# MusselTracker2_RevC.net
KiCad netlist of a schematic drawn in EAGLE
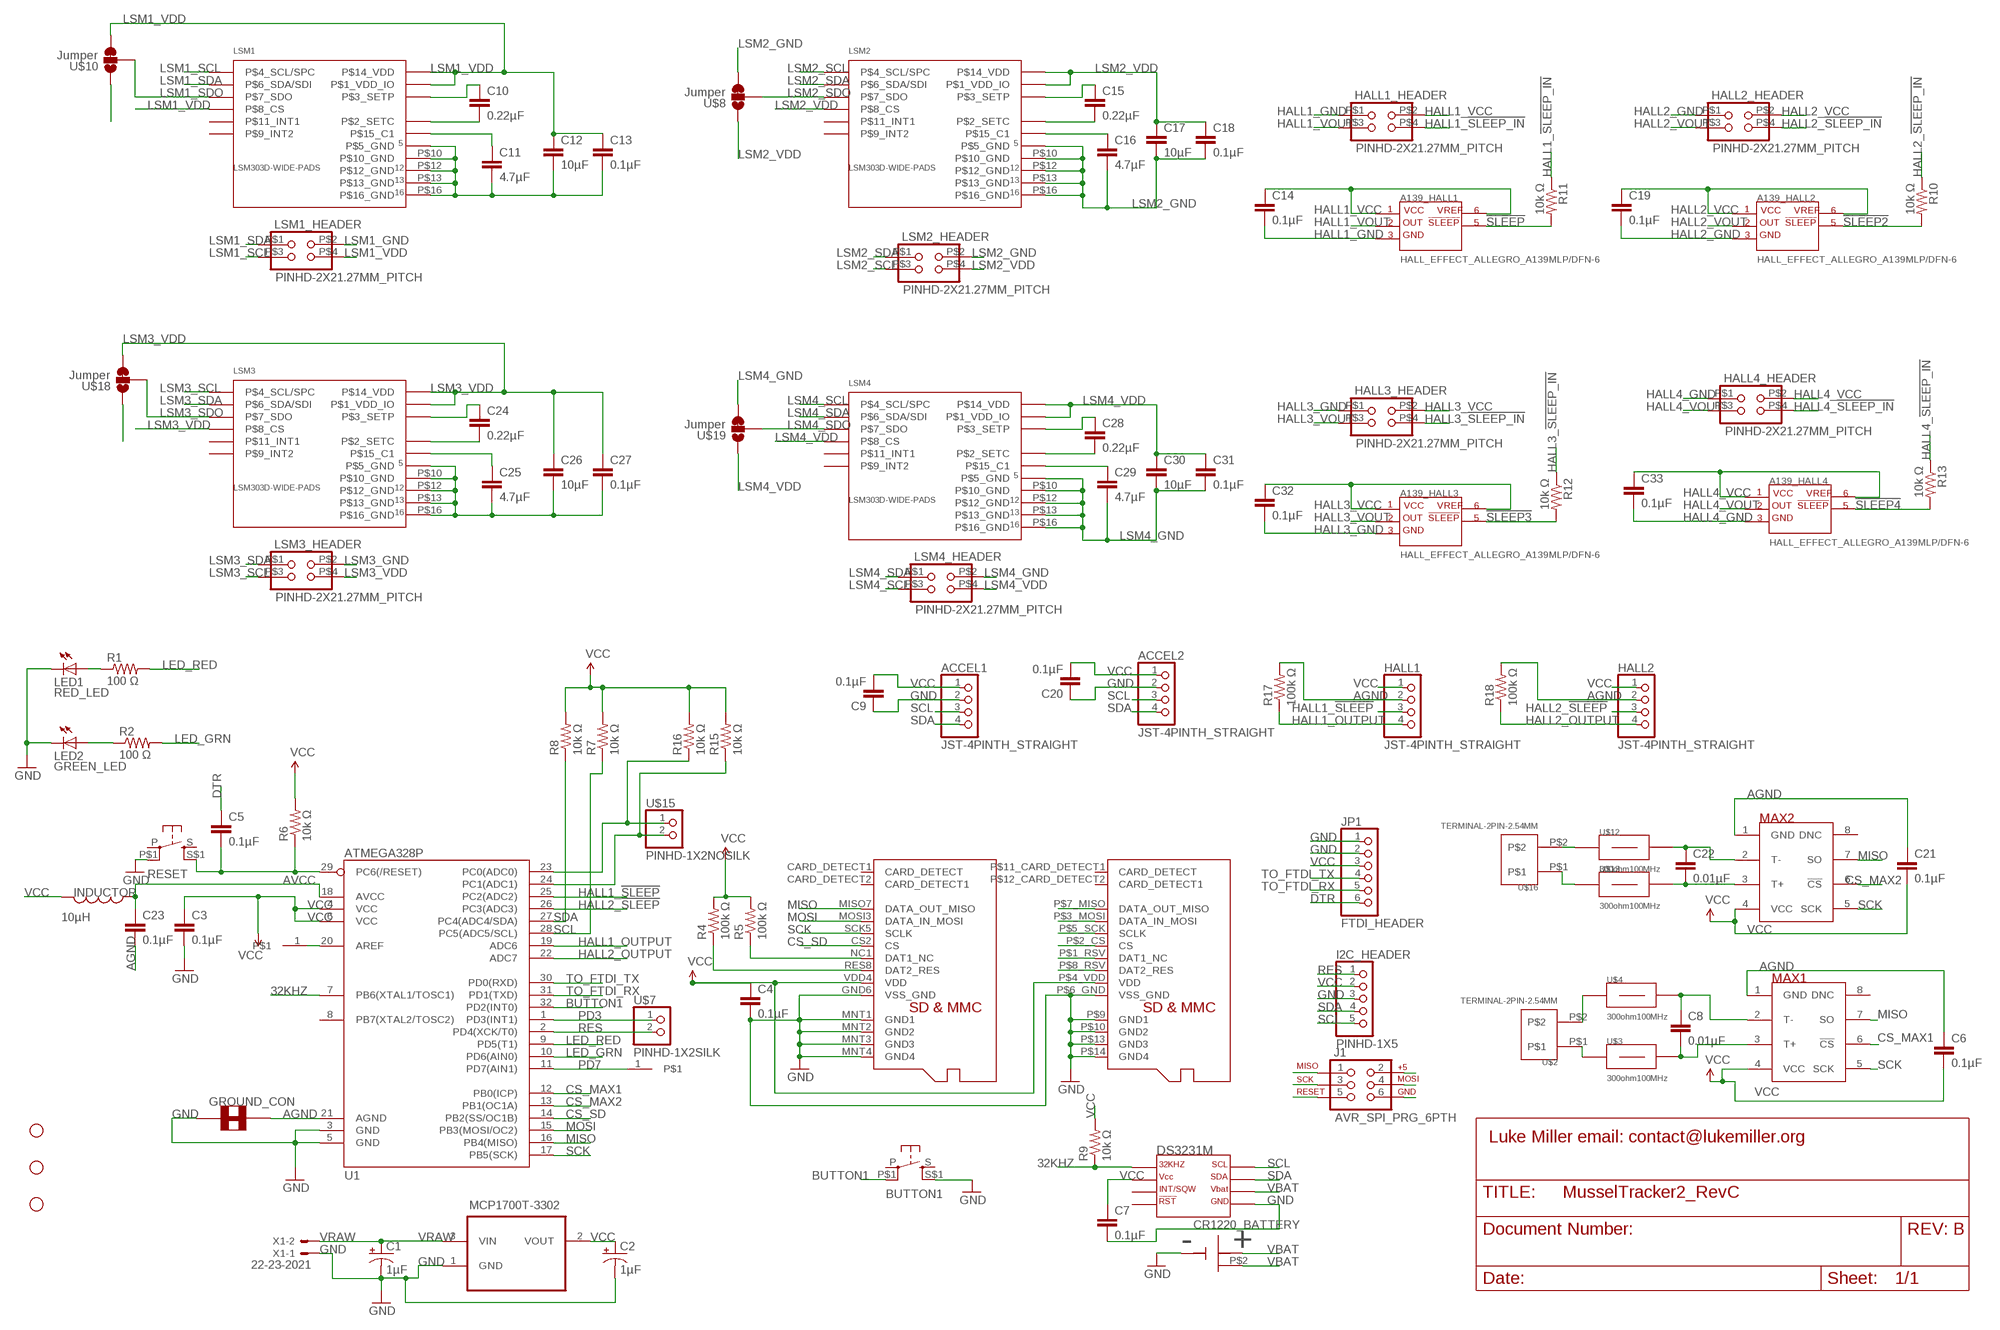
[diagram p0: schematic, sheet 1]

(export (version "E")
  (design (tool "Eeschema 10.0.6"))
  (components
    (comp (ref "A139_HALL1")
      (value "HALL_EFFECT_ALLEGRO_A139MLP/DFN-6")
      (footprint "eagle-import:A139__HALL_EFFECT")
      (libsource (lib "eagle-import") (part "HALL_EFFECT_ALLEGRO_A139MLP/DFN-6"))
    )
    (comp (ref "A139_HALL2")
      (value "HALL_EFFECT_ALLEGRO_A139MLP/DFN-6")
      (footprint "eagle-import:A139__HALL_EFFECT")
      (libsource (lib "eagle-import") (part "HALL_EFFECT_ALLEGRO_A139MLP/DFN-6"))
    )
    (comp (ref "A139_HALL3")
      (value "HALL_EFFECT_ALLEGRO_A139MLP/DFN-6")
      (footprint "eagle-import:A139__HALL_EFFECT")
      (libsource (lib "eagle-import") (part "HALL_EFFECT_ALLEGRO_A139MLP/DFN-6"))
    )
    (comp (ref "A139_HALL4")
      (value "HALL_EFFECT_ALLEGRO_A139MLP/DFN-6")
      (footprint "eagle-import:A139__HALL_EFFECT")
      (libsource (lib "eagle-import") (part "HALL_EFFECT_ALLEGRO_A139MLP/DFN-6"))
    )
    (comp (ref "ACCEL1")
      (value "JST-4PINTH_STRAIGHT")
      (footprint "eagle-import:JST-PH-4-THM")
      (libsource (lib "eagle-import") (part "JST-4PINTH_STRAIGHT"))
    )
    (comp (ref "ACCEL2")
      (value "JST-4PINTH_STRAIGHT")
      (footprint "eagle-import:JST-PH-4-THM")
      (libsource (lib "eagle-import") (part "JST-4PINTH_STRAIGHT"))
    )
    (comp (ref "BUTTON1")
      (value "PUSHBUTTON_DPST_SMD")
      (footprint "eagle-import:PUSHBUTTON_DPST_SMD")
      (libsource (lib "eagle-import") (part "PUSHBUTTON_DPST_SMD"))
    )
    (comp (ref "C1")
      (value "1µF")
      (footprint "eagle-import:PANASONIC_B")
      (libsource (lib "eagle-import") (part "CPOL-USB"))
    )
    (comp (ref "C2")
      (value "1µF")
      (footprint "eagle-import:PANASONIC_B")
      (libsource (lib "eagle-import") (part "CPOL-USB"))
    )
    (comp (ref "C3")
      (value "0.1µF")
      (footprint "eagle-import:0805")
      (libsource (lib "eagle-import") (part "CAP0805"))
    )
    (comp (ref "C4")
      (value "0.1µF")
      (footprint "eagle-import:0805")
      (libsource (lib "eagle-import") (part "CAP0805"))
    )
    (comp (ref "C5")
      (value "0.1µF")
      (footprint "eagle-import:0805")
      (libsource (lib "eagle-import") (part "CAP0805"))
    )
    (comp (ref "C6")
      (value "0.1µF")
      (footprint "eagle-import:0805")
      (libsource (lib "eagle-import") (part "CAP0805"))
    )
    (comp (ref "C7")
      (value "0.1µF")
      (footprint "eagle-import:0805")
      (libsource (lib "eagle-import") (part "CAP0805"))
    )
    (comp (ref "C8")
      (value "0.01µF")
      (footprint "eagle-import:0805_CAP_50V_KEMET")
      (libsource (lib "eagle-import") (part "CAP0805_KEMET"))
    )
    (comp (ref "C9")
      (value "0.1µF")
      (footprint "eagle-import:0805")
      (libsource (lib "eagle-import") (part "CAP0805"))
    )
    (comp (ref "C10")
      (value "0.22µF")
      (footprint "eagle-import:0805")
      (libsource (lib "eagle-import") (part "CAP0805"))
    )
    (comp (ref "C11")
      (value "4.7µF")
      (footprint "eagle-import:0805")
      (libsource (lib "eagle-import") (part "CAP0805"))
    )
    (comp (ref "C12")
      (value "10µF")
      (footprint "eagle-import:0805")
      (libsource (lib "eagle-import") (part "CAP0805"))
    )
    (comp (ref "C13")
      (value "0.1µF")
      (footprint "eagle-import:0805")
      (libsource (lib "eagle-import") (part "CAP0805"))
    )
    (comp (ref "C14")
      (value "0.1µF")
      (footprint "eagle-import:0805")
      (libsource (lib "eagle-import") (part "CAP0805"))
    )
    (comp (ref "C15")
      (value "0.22µF")
      (footprint "eagle-import:0805")
      (libsource (lib "eagle-import") (part "CAP0805"))
    )
    (comp (ref "C16")
      (value "4.7µF")
      (footprint "eagle-import:0805")
      (libsource (lib "eagle-import") (part "CAP0805"))
    )
    (comp (ref "C17")
      (value "10µF")
      (footprint "eagle-import:0805")
      (libsource (lib "eagle-import") (part "CAP0805"))
    )
    (comp (ref "C18")
      (value "0.1µF")
      (footprint "eagle-import:0805")
      (libsource (lib "eagle-import") (part "CAP0805"))
    )
    (comp (ref "C19")
      (value "0.1µF")
      (footprint "eagle-import:0805")
      (libsource (lib "eagle-import") (part "CAP0805"))
    )
    (comp (ref "C20")
      (value "0.1µF")
      (footprint "eagle-import:0805")
      (libsource (lib "eagle-import") (part "CAP0805"))
    )
    (comp (ref "C21")
      (value "0.1µF")
      (footprint "eagle-import:0805")
      (libsource (lib "eagle-import") (part "CAP0805"))
    )
    (comp (ref "C22")
      (value "0.01µF")
      (footprint "eagle-import:0805_CAP_50V_KEMET")
      (libsource (lib "eagle-import") (part "CAP0805_KEMET"))
    )
    (comp (ref "C23")
      (value "0.1µF")
      (footprint "eagle-import:0805")
      (libsource (lib "eagle-import") (part "CAP0805"))
    )
    (comp (ref "C24")
      (value "0.22µF")
      (footprint "eagle-import:0805")
      (libsource (lib "eagle-import") (part "CAP0805"))
    )
    (comp (ref "C25")
      (value "4.7µF")
      (footprint "eagle-import:0805")
      (libsource (lib "eagle-import") (part "CAP0805"))
    )
    (comp (ref "C26")
      (value "10µF")
      (footprint "eagle-import:0805")
      (libsource (lib "eagle-import") (part "CAP0805"))
    )
    (comp (ref "C27")
      (value "0.1µF")
      (footprint "eagle-import:0805")
      (libsource (lib "eagle-import") (part "CAP0805"))
    )
    (comp (ref "C28")
      (value "0.22µF")
      (footprint "eagle-import:0805")
      (libsource (lib "eagle-import") (part "CAP0805"))
    )
    (comp (ref "C29")
      (value "4.7µF")
      (footprint "eagle-import:0805")
      (libsource (lib "eagle-import") (part "CAP0805"))
    )
    (comp (ref "C30")
      (value "10µF")
      (footprint "eagle-import:0805")
      (libsource (lib "eagle-import") (part "CAP0805"))
    )
    (comp (ref "C31")
      (value "0.1µF")
      (footprint "eagle-import:0805")
      (libsource (lib "eagle-import") (part "CAP0805"))
    )
    (comp (ref "C32")
      (value "0.1µF")
      (footprint "eagle-import:0805")
      (libsource (lib "eagle-import") (part "CAP0805"))
    )
    (comp (ref "C33")
      (value "0.1µF")
      (footprint "eagle-import:0805")
      (libsource (lib "eagle-import") (part "CAP0805"))
    )
    (comp (ref "CR1220_BATTERY")
      (value "CR1220_BATTERY_HOLDERSMD")
      (footprint "eagle-import:CR1220_BATTERY_HOLDER_SMD")
      (libsource (lib "eagle-import") (part "CR1220_BATTERY_HOLDERSMD"))
    )
    (comp (ref "DS3231M")
      (value "DS3231MSOIC-8")
      (footprint "eagle-import:DS3231M_SOIC8")
      (libsource (lib "eagle-import") (part "DS3231MSOIC-8"))
    )
    (comp (ref "GROUND_CON")
      (value "SOLDER_JUMPER_TRACESTANDARD")
      (footprint "eagle-import:SJ_2S-TRACE")
      (libsource (lib "eagle-import") (part "SOLDER_JUMPER_TRACESTANDARD"))
    )
    (comp (ref "HALL1")
      (value "JST-4PINTH_STRAIGHT")
      (footprint "eagle-import:JST-PH-4-THM")
      (libsource (lib "eagle-import") (part "JST-4PINTH_STRAIGHT"))
    )
    (comp (ref "HALL1_HEADER")
      (value "PINHD-2X21.27MM_PITCH")
      (footprint "eagle-import:2X2_1.27MM")
      (libsource (lib "eagle-import") (part "PINHD-2X21.27MM_PITCH"))
    )
    (comp (ref "HALL2")
      (value "JST-4PINTH_STRAIGHT")
      (footprint "eagle-import:JST-PH-4-THM")
      (libsource (lib "eagle-import") (part "JST-4PINTH_STRAIGHT"))
    )
    (comp (ref "HALL2_HEADER")
      (value "PINHD-2X21.27MM_PITCH")
      (footprint "eagle-import:2X2_1.27MM")
      (libsource (lib "eagle-import") (part "PINHD-2X21.27MM_PITCH"))
    )
    (comp (ref "HALL3_HEADER")
      (value "PINHD-2X21.27MM_PITCH")
      (footprint "eagle-import:2X2_1.27MM")
      (libsource (lib "eagle-import") (part "PINHD-2X21.27MM_PITCH"))
    )
    (comp (ref "HALL4_HEADER")
      (value "PINHD-2X21.27MM_PITCH")
      (footprint "eagle-import:2X2_1.27MM")
      (libsource (lib "eagle-import") (part "PINHD-2X21.27MM_PITCH"))
    )
    (comp (ref "I2C_HEADER")
      (value "PINHD-1X5")
      (footprint "eagle-import:1X05_BIGLOCK")
      (libsource (lib "eagle-import") (part "PINHD-1X5"))
    )
    (comp (ref "INDUCTOR")
      (value "10µH")
      (footprint "eagle-import:I_0805")
      (libsource (lib "eagle-import") (part "INDUCTOR0805_TY"))
    )
    (comp (ref "J1")
      (value "AVR_SPI_PRG_6PTH")
      (footprint "eagle-import:2X3")
      (libsource (lib "eagle-import") (part "AVR_SPI_PRG_6PTH"))
    )
    (comp (ref "JP1")
      (value "FTDI_HEADER")
      (footprint "eagle-import:1X06-BIGLOCK")
      (libsource (lib "eagle-import") (part "PINHD-1X6LOCK"))
    )
    (comp (ref "LED1")
      (value "RED_LED")
      (footprint "eagle-import:CHIPLED_0805")
      (libsource (lib "eagle-import") (part "LED0805"))
    )
    (comp (ref "LED2")
      (value "GREEN_LED")
      (footprint "eagle-import:CHIPLED_0805")
      (libsource (lib "eagle-import") (part "LED0805"))
    )
    (comp (ref "LSM1")
      (value "LSM303D-WIDE-PADS")
      (footprint "eagle-import:LSM303D")
      (libsource (lib "eagle-import") (part "LSM303D-WIDE-PADS"))
    )
    (comp (ref "LSM1_HEADER")
      (value "PINHD-2X21.27MM_PITCH")
      (footprint "eagle-import:2X2_1.27MM")
      (libsource (lib "eagle-import") (part "PINHD-2X21.27MM_PITCH"))
    )
    (comp (ref "LSM2")
      (value "LSM303D-WIDE-PADS")
      (footprint "eagle-import:LSM303D")
      (libsource (lib "eagle-import") (part "LSM303D-WIDE-PADS"))
    )
    (comp (ref "LSM2_HEADER")
      (value "PINHD-2X21.27MM_PITCH")
      (footprint "eagle-import:2X2_1.27MM")
      (libsource (lib "eagle-import") (part "PINHD-2X21.27MM_PITCH"))
    )
    (comp (ref "LSM3")
      (value "LSM303D-WIDE-PADS")
      (footprint "eagle-import:LSM303D")
      (libsource (lib "eagle-import") (part "LSM303D-WIDE-PADS"))
    )
    (comp (ref "LSM3_HEADER")
      (value "PINHD-2X21.27MM_PITCH")
      (footprint "eagle-import:2X2_1.27MM")
      (libsource (lib "eagle-import") (part "PINHD-2X21.27MM_PITCH"))
    )
    (comp (ref "LSM4")
      (value "LSM303D-WIDE-PADS")
      (footprint "eagle-import:LSM303D")
      (libsource (lib "eagle-import") (part "LSM303D-WIDE-PADS"))
    )
    (comp (ref "LSM4_HEADER")
      (value "PINHD-2X21.27MM_PITCH")
      (footprint "eagle-import:2X2_1.27MM")
      (libsource (lib "eagle-import") (part "PINHD-2X21.27MM_PITCH"))
    )
    (comp (ref "MAX1")
      (value "MAX31855")
      (footprint "eagle-import:SO08")
      (libsource (lib "eagle-import") (part "MAX31855"))
    )
    (comp (ref "MAX2")
      (value "MAX31855")
      (footprint "eagle-import:SO08")
      (libsource (lib "eagle-import") (part "MAX31855"))
    )
    (comp (ref "MCP1700T-3302")
      (value "MCP1700T-3302E/TT")
      (footprint "eagle-import:SOT95P237X112-3N")
      (libsource (lib "eagle-import") (part "MCP1700T-3302E/TT"))
    )
    (comp (ref "R1")
      (value "100 Ω")
      (footprint "eagle-import:R0805")
      (libsource (lib "eagle-import") (part "RESISTOR_SMDR0805"))
    )
    (comp (ref "R2")
      (value "100 Ω")
      (footprint "eagle-import:R0805")
      (libsource (lib "eagle-import") (part "RESISTOR_SMDR0805"))
    )
    (comp (ref "R4")
      (value "100k Ω")
      (footprint "eagle-import:R0805")
      (libsource (lib "eagle-import") (part "RESISTOR_SMDR0805"))
    )
    (comp (ref "R5")
      (value "100k Ω")
      (footprint "eagle-import:R0805")
      (libsource (lib "eagle-import") (part "RESISTOR_SMDR0805"))
    )
    (comp (ref "R6")
      (value "10k Ω")
      (footprint "eagle-import:R0805")
      (libsource (lib "eagle-import") (part "RESISTOR_SMDR0805"))
    )
    (comp (ref "R7")
      (value "10k Ω")
      (footprint "eagle-import:R0805")
      (libsource (lib "eagle-import") (part "RESISTOR_SMDR0805"))
    )
    (comp (ref "R8")
      (value "10k Ω")
      (footprint "eagle-import:R0805")
      (libsource (lib "eagle-import") (part "RESISTOR_SMDR0805"))
    )
    (comp (ref "R9")
      (value "10k Ω")
      (footprint "eagle-import:R0805")
      (libsource (lib "eagle-import") (part "RESISTOR_SMDR0805"))
    )
    (comp (ref "R10")
      (value "10k Ω")
      (footprint "eagle-import:R0805")
      (libsource (lib "eagle-import") (part "RESISTOR_SMDR0805"))
    )
    (comp (ref "R11")
      (value "10k Ω")
      (footprint "eagle-import:R0805")
      (libsource (lib "eagle-import") (part "RESISTOR_SMDR0805"))
    )
    (comp (ref "R12")
      (value "10k Ω")
      (footprint "eagle-import:R0805")
      (libsource (lib "eagle-import") (part "RESISTOR_SMDR0805"))
    )
    (comp (ref "R13")
      (value "10k Ω")
      (footprint "eagle-import:R0805")
      (libsource (lib "eagle-import") (part "RESISTOR_SMDR0805"))
    )
    (comp (ref "R15")
      (value "10k Ω")
      (footprint "eagle-import:R0805")
      (libsource (lib "eagle-import") (part "RESISTOR_SMDR0805"))
    )
    (comp (ref "R16")
      (value "10k Ω")
      (footprint "eagle-import:R0805")
      (libsource (lib "eagle-import") (part "RESISTOR_SMDR0805"))
    )
    (comp (ref "R17")
      (value "100k Ω")
      (footprint "eagle-import:R0805")
      (libsource (lib "eagle-import") (part "RESISTOR_SMDR0805"))
    )
    (comp (ref "R18")
      (value "100k Ω")
      (footprint "eagle-import:R0805")
      (libsource (lib "eagle-import") (part "RESISTOR_SMDR0805"))
    )
    (comp (ref "RESET")
      (value "PUSHBUTTON_DPST_SMD")
      (footprint "eagle-import:PUSHBUTTON_DPST_SMD")
      (libsource (lib "eagle-import") (part "PUSHBUTTON_DPST_SMD"))
    )
    (comp (ref "STANDOFF1")
      (value "STAND-OFF")
      (footprint "eagle-import:STAND-OFF")
      (libsource (lib "eagle-import") (part "STAND-OFF"))
    )
    (comp (ref "STANDOFF2")
      (value "STAND-OFF")
      (footprint "eagle-import:STAND-OFF")
      (libsource (lib "eagle-import") (part "STAND-OFF"))
    )
    (comp (ref "STANDOFF3")
      (value "STAND-OFF")
      (footprint "eagle-import:STAND-OFF")
      (libsource (lib "eagle-import") (part "STAND-OFF"))
    )
    (comp (ref "U$1")
      (value "MICROSD_MOLEX_REVERSECURRENT")
      (footprint "eagle-import:MICROSD_SOCKET_MOLEX_REVERSEMOUNT")
      (libsource (lib "eagle-import") (part "MICROSD_MOLEX_REVERSECURRENT"))
    )
    (comp (ref "U$2")
      (value "TERMINAL-2PIN-2.54MM")
      (footprint "eagle-import:TERMINAL-2PIN-2.54MM")
      (libsource (lib "eagle-import") (part "TERMINAL-2PIN-2.54MM"))
    )
    (comp (ref "U$3")
      (value "300ohm100MHz")
      (footprint "eagle-import:0805")
      (libsource (lib "eagle-import") (part "FERRITE_BEAD0805"))
    )
    (comp (ref "U$4")
      (value "300ohm100MHz")
      (footprint "eagle-import:0805")
      (libsource (lib "eagle-import") (part "FERRITE_BEAD0805"))
    )
    (comp (ref "U$6")
      (value "PINHD-1X1SMALL")
      (footprint "eagle-import:1X01_SMALL")
      (libsource (lib "eagle-import") (part "PINHD-1X1SMALL"))
    )
    (comp (ref "U$7")
      (value "PINHD-1X2SILK")
      (footprint "eagle-import:1X02")
      (libsource (lib "eagle-import") (part "PINHD-1X2SILK"))
    )
    (comp (ref "U$8")
      (value "Jumper")
      (footprint "eagle-import:PAD-JUMPER-3-2OF3_NC_BY_TRACE_SMALL")
      (libsource (lib "eagle-import") (part "SOLDER_JUMPER_3_2OF3_NORMALLY_CLOSED_BY_TRACESMALL"))
    )
    (comp (ref "U$10")
      (value "Jumper")
      (footprint "eagle-import:PAD-JUMPER-3-2OF3_NC_BY_TRACE_SMALL")
      (libsource (lib "eagle-import") (part "SOLDER_JUMPER_3_2OF3_NORMALLY_CLOSED_BY_TRACESMALL"))
    )
    (comp (ref "U$12")
      (value "300ohm100MHz")
      (footprint "eagle-import:0805")
      (libsource (lib "eagle-import") (part "FERRITE_BEAD0805"))
    )
    (comp (ref "U$13")
      (value "300ohm100MHz")
      (footprint "eagle-import:0805")
      (libsource (lib "eagle-import") (part "FERRITE_BEAD0805"))
    )
    (comp (ref "U$14")
      (value "MICROSD_MOLEX_REVERSEOBSOLETE")
      (footprint "eagle-import:MICROSD_SOCKET_MOLEX_REVERSEMOUNT_OBSOLETE")
      (libsource (lib "eagle-import") (part "MICROSD_MOLEX_REVERSEOBSOLETE"))
    )
    (comp (ref "U$15")
      (value "PINHD-1X2NOSILK")
      (footprint "eagle-import:1X02_NOSILK")
      (libsource (lib "eagle-import") (part "PINHD-1X2NOSILK"))
    )
    (comp (ref "U$16")
      (value "TERMINAL-2PIN-2.54MM")
      (footprint "eagle-import:TERMINAL-2PIN-2.54MM")
      (libsource (lib "eagle-import") (part "TERMINAL-2PIN-2.54MM"))
    )
    (comp (ref "U$17")
      (value "PINHD-1X1SMALL")
      (footprint "eagle-import:1X01_SMALL")
      (libsource (lib "eagle-import") (part "PINHD-1X1SMALL"))
    )
    (comp (ref "U$18")
      (value "Jumper")
      (footprint "eagle-import:PAD-JUMPER-3-2OF3_NC_BY_TRACE_SMALL")
      (libsource (lib "eagle-import") (part "SOLDER_JUMPER_3_2OF3_NORMALLY_CLOSED_BY_TRACESMALL"))
    )
    (comp (ref "U$19")
      (value "Jumper")
      (footprint "eagle-import:PAD-JUMPER-3-2OF3_NC_BY_TRACE_SMALL")
      (libsource (lib "eagle-import") (part "SOLDER_JUMPER_3_2OF3_NORMALLY_CLOSED_BY_TRACESMALL"))
    )
    (comp (ref "U1")
      (value "ATMEGA328P")
      (footprint "eagle-import:TQFP32-08")
      (libsource (lib "eagle-import") (part "ATMEGA328_SMT"))
    )
    (comp (ref "X1")
      (value "22-23-2021")
      (footprint "eagle-import:22-23-2021")
      (fields (field (name "MF") "MOLEX"))
      (libsource (lib "eagle-import") (part "22-23-2021"))
    )
  )
  (nets
    (net (code "1") (name "/32KHZ") (class "Default")
      (node (ref "DS3231M") (pin "1") (pinfunction "P$1_32KHZ_1") (pintype "bidirectional"))
      (node (ref "R9") (pin "1") (pinfunction "1_1") (pintype "passive"))
      (node (ref "U1") (pin "7") (pinfunction "PB6(XTAL1/TOSC1)_7") (pintype "bidirectional"))
    )
    (net (code "2") (name "/AGND") (class "Default")
      (node (ref "C21") (pin "1") (pinfunction "1_1") (pintype "passive"))
      (node (ref "C23") (pin "2") (pinfunction "2_2") (pintype "passive"))
      (node (ref "C6") (pin "1") (pinfunction "1_1") (pintype "passive"))
      (node (ref "GROUND_CON") (pin "2") (pinfunction "P$2_2") (pintype "bidirectional"))
      (node (ref "HALL1") (pin "2") (pinfunction "2_2") (pintype "passive"))
      (node (ref "HALL2") (pin "2") (pinfunction "2_2") (pintype "passive"))
      (node (ref "MAX1") (pin "1") (pinfunction "GND_1") (pintype "power_in"))
      (node (ref "MAX2") (pin "1") (pinfunction "GND_1") (pintype "power_in"))
      (node (ref "R17") (pin "2") (pinfunction "2_2") (pintype "passive"))
      (node (ref "R18") (pin "2") (pinfunction "2_2") (pintype "passive"))
      (node (ref "U1") (pin "21") (pinfunction "AGND_21") (pintype "bidirectional"))
    )
    (net (code "3") (name "/AVCC") (class "Default")
      (node (ref "C23") (pin "1") (pinfunction "1_1") (pintype "passive"))
      (node (ref "INDUCTOR") (pin "P$1") (pinfunction "1_P$1") (pintype "passive"))
      (node (ref "U1") (pin "18") (pinfunction "AVCC_18") (pintype "bidirectional"))
    )
    (net (code "4") (name "/BUTTON1") (class "Default")
      (node (ref "BUTTON1") (pin "P$1") (pinfunction "P1_P$1") (pintype "passive"))
      (node (ref "U1") (pin "32") (pinfunction "PD2(INT0)_32") (pintype "bidirectional"))
    )
    (net (code "5") (name "/CS_MAX1") (class "Default")
      (node (ref "MAX1") (pin "6") (pinfunction "~{CS}_6") (pintype "bidirectional"))
      (node (ref "U1") (pin "12") (pinfunction "PB0(ICP)_12") (pintype "bidirectional"))
    )
    (net (code "6") (name "/CS_MAX2") (class "Default")
      (node (ref "MAX2") (pin "6") (pinfunction "~{CS}_6") (pintype "bidirectional"))
      (node (ref "U1") (pin "13") (pinfunction "PB1(OC1A)_13") (pintype "bidirectional"))
    )
    (net (code "7") (name "/CS_SD") (class "Default")
      (node (ref "U$1") (pin "CS2") (pinfunction "CS_CS2") (pintype "input"))
      (node (ref "U$14") (pin "P$2_CS") (pinfunction "CS_P$2_CS") (pintype "input"))
      (node (ref "U1") (pin "14") (pinfunction "PB2(SS/OC1B)_14") (pintype "bidirectional"))
    )
    (net (code "8") (name "/DTR") (class "Default")
      (node (ref "C5") (pin "1") (pinfunction "1_1") (pintype "passive"))
      (node (ref "JP1") (pin "6") (pinfunction "6_6") (pintype "passive"))
    )
    (net (code "9") (name "/HALL1_GND") (class "Default")
      (node (ref "A139_HALL1") (pin "P$3_4") (pinfunction "P$3_P$3_4") (pintype "bidirectional"))
      (node (ref "C14") (pin "2") (pinfunction "2_2") (pintype "passive"))
      (node (ref "HALL1_HEADER") (pin "P$1") (pinfunction "1_P$1") (pintype "passive"))
    )
    (net (code "10") (name "/HALL1_OUTPUT") (class "Default")
      (node (ref "HALL1") (pin "4") (pinfunction "4_4") (pintype "passive"))
      (node (ref "R17") (pin "1") (pinfunction "1_1") (pintype "passive"))
      (node (ref "U1") (pin "19") (pinfunction "ADC6_19") (pintype "bidirectional"))
    )
    (net (code "11") (name "/HALL1_VCC") (class "Default")
      (node (ref "A139_HALL1") (pin "P$1") (pinfunction "P$1_P$1") (pintype "bidirectional"))
      (node (ref "A139_HALL1") (pin "P$6") (pinfunction "P$6_P$6") (pintype "bidirectional"))
      (node (ref "C14") (pin "1") (pinfunction "1_1") (pintype "passive"))
      (node (ref "HALL1_HEADER") (pin "P$2") (pinfunction "2_P$2") (pintype "passive"))
    )
    (net (code "12") (name "/HALL1_VOUT") (class "Default")
      (node (ref "A139_HALL1") (pin "P$2") (pinfunction "P$2_P$2") (pintype "bidirectional"))
      (node (ref "HALL1_HEADER") (pin "P$3") (pinfunction "3_P$3") (pintype "passive"))
    )
    (net (code "13") (name "/HALL1_~{SLEEP_IN}") (class "Default")
      (node (ref "HALL1_HEADER") (pin "P$4") (pinfunction "4_P$4") (pintype "passive"))
      (node (ref "R11") (pin "1") (pinfunction "1_1") (pintype "passive"))
    )
    (net (code "14") (name "/HALL1_~{SLEEP}") (class "Default")
      (node (ref "HALL1") (pin "3") (pinfunction "3_3") (pintype "passive"))
      (node (ref "U1") (pin "25") (pinfunction "PC2(ADC2)_25") (pintype "bidirectional"))
    )
    (net (code "15") (name "/HALL2_GND") (class "Default")
      (node (ref "A139_HALL2") (pin "P$3_4") (pinfunction "P$3_P$3_4") (pintype "bidirectional"))
      (node (ref "C19") (pin "2") (pinfunction "2_2") (pintype "passive"))
      (node (ref "HALL2_HEADER") (pin "P$1") (pinfunction "1_P$1") (pintype "passive"))
    )
    (net (code "16") (name "/HALL2_OUTPUT") (class "Default")
      (node (ref "HALL2") (pin "4") (pinfunction "4_4") (pintype "passive"))
      (node (ref "R18") (pin "1") (pinfunction "1_1") (pintype "passive"))
      (node (ref "U1") (pin "22") (pinfunction "ADC7_22") (pintype "bidirectional"))
    )
    (net (code "17") (name "/HALL2_VCC") (class "Default")
      (node (ref "A139_HALL2") (pin "P$1") (pinfunction "P$1_P$1") (pintype "bidirectional"))
      (node (ref "A139_HALL2") (pin "P$6") (pinfunction "P$6_P$6") (pintype "bidirectional"))
      (node (ref "C19") (pin "1") (pinfunction "1_1") (pintype "passive"))
      (node (ref "HALL2_HEADER") (pin "P$2") (pinfunction "2_P$2") (pintype "passive"))
    )
    (net (code "18") (name "/HALL2_VOUT") (class "Default")
      (node (ref "A139_HALL2") (pin "P$2") (pinfunction "P$2_P$2") (pintype "bidirectional"))
      (node (ref "HALL2_HEADER") (pin "P$3") (pinfunction "3_P$3") (pintype "passive"))
    )
    (net (code "19") (name "/HALL2_~{SLEEP_IN}") (class "Default")
      (node (ref "HALL2_HEADER") (pin "P$4") (pinfunction "4_P$4") (pintype "passive"))
      (node (ref "R10") (pin "1") (pinfunction "1_1") (pintype "passive"))
    )
    (net (code "20") (name "/HALL2_~{SLEEP}") (class "Default")
      (node (ref "HALL2") (pin "3") (pinfunction "3_3") (pintype "passive"))
      (node (ref "U1") (pin "26") (pinfunction "PC3(ADC3)_26") (pintype "bidirectional"))
    )
    (net (code "21") (name "/HALL3_GND") (class "Default")
      (node (ref "A139_HALL3") (pin "P$3_4") (pinfunction "P$3_P$3_4") (pintype "bidirectional"))
      (node (ref "C32") (pin "2") (pinfunction "2_2") (pintype "passive"))
      (node (ref "HALL3_HEADER") (pin "P$1") (pinfunction "1_P$1") (pintype "passive"))
    )
    (net (code "22") (name "/HALL3_VCC") (class "Default")
      (node (ref "A139_HALL3") (pin "P$1") (pinfunction "P$1_P$1") (pintype "bidirectional"))
      (node (ref "A139_HALL3") (pin "P$6") (pinfunction "P$6_P$6") (pintype "bidirectional"))
      (node (ref "C32") (pin "1") (pinfunction "1_1") (pintype "passive"))
      (node (ref "HALL3_HEADER") (pin "P$2") (pinfunction "2_P$2") (pintype "passive"))
    )
    (net (code "23") (name "/HALL3_VOUT") (class "Default")
      (node (ref "A139_HALL3") (pin "P$2") (pinfunction "P$2_P$2") (pintype "bidirectional"))
      (node (ref "HALL3_HEADER") (pin "P$3") (pinfunction "3_P$3") (pintype "passive"))
    )
    (net (code "24") (name "/HALL3_~{SLEEP_IN}") (class "Default")
      (node (ref "HALL3_HEADER") (pin "P$4") (pinfunction "4_P$4") (pintype "passive"))
      (node (ref "R12") (pin "1") (pinfunction "1_1") (pintype "passive"))
    )
    (net (code "25") (name "/HALL4_GND") (class "Default")
      (node (ref "A139_HALL4") (pin "P$3_4") (pinfunction "P$3_P$3_4") (pintype "bidirectional"))
      (node (ref "C33") (pin "2") (pinfunction "2_2") (pintype "passive"))
      (node (ref "HALL4_HEADER") (pin "P$1") (pinfunction "1_P$1") (pintype "passive"))
    )
    (net (code "26") (name "/HALL4_VCC") (class "Default")
      (node (ref "A139_HALL4") (pin "P$1") (pinfunction "P$1_P$1") (pintype "bidirectional"))
      (node (ref "A139_HALL4") (pin "P$6") (pinfunction "P$6_P$6") (pintype "bidirectional"))
      (node (ref "C33") (pin "1") (pinfunction "1_1") (pintype "passive"))
      (node (ref "HALL4_HEADER") (pin "P$2") (pinfunction "2_P$2") (pintype "passive"))
    )
    (net (code "27") (name "/HALL4_VOUT") (class "Default")
      (node (ref "A139_HALL4") (pin "P$2") (pinfunction "P$2_P$2") (pintype "bidirectional"))
      (node (ref "HALL4_HEADER") (pin "P$3") (pinfunction "3_P$3") (pintype "passive"))
    )
    (net (code "28") (name "/HALL4_~{SLEEP_IN}") (class "Default")
      (node (ref "HALL4_HEADER") (pin "P$4") (pinfunction "4_P$4") (pintype "passive"))
      (node (ref "R13") (pin "1") (pinfunction "1_1") (pintype "passive"))
    )
    (net (code "29") (name "/LED_GRN") (class "Default")
      (node (ref "R2") (pin "2") (pinfunction "2_2") (pintype "passive"))
      (node (ref "U1") (pin "10") (pinfunction "PD6(AIN0)_10") (pintype "bidirectional"))
    )
    (net (code "30") (name "/LED_RED") (class "Default")
      (node (ref "R1") (pin "2") (pinfunction "2_2") (pintype "passive"))
      (node (ref "U1") (pin "9") (pinfunction "PD5(T1)_9") (pintype "bidirectional"))
    )
    (net (code "31") (name "/LSM1_GND") (class "Default")
      (node (ref "C11") (pin "2") (pinfunction "2_2") (pintype "passive"))
      (node (ref "C12") (pin "2") (pinfunction "2_2") (pintype "passive"))
      (node (ref "C13") (pin "2") (pinfunction "2_2") (pintype "passive"))
      (node (ref "LSM1") (pin "P$10") (pinfunction "P$10_GND_P$10") (pintype "bidirectional"))
      (node (ref "LSM1") (pin "P$12") (pinfunction "P$12_GND_P$12") (pintype "bidirectional"))
      (node (ref "LSM1") (pin "P$13") (pinfunction "P$13_GND_P$13") (pintype "bidirectional"))
      (node (ref "LSM1") (pin "P$16") (pinfunction "P$16_GND_P$16") (pintype "bidirectional"))
      (node (ref "LSM1") (pin "P$5") (pinfunction "P$5_GND_P$5") (pintype "power_in"))
      (node (ref "LSM1_HEADER") (pin "P$2") (pinfunction "2_P$2") (pintype "passive"))
      (node (ref "U$10") (pin "1") (pinfunction "1_1") (pintype "passive"))
    )
    (net (code "32") (name "/LSM1_SCL") (class "Default")
      (node (ref "LSM1") (pin "P$4") (pinfunction "P$4_SCL/SPC_P$4") (pintype "bidirectional"))
      (node (ref "LSM1_HEADER") (pin "P$3") (pinfunction "3_P$3") (pintype "passive"))
    )
    (net (code "33") (name "/LSM1_SDA") (class "Default")
      (node (ref "LSM1") (pin "P$6") (pinfunction "P$6_SDA/SDI_P$6") (pintype "bidirectional"))
      (node (ref "LSM1_HEADER") (pin "P$1") (pinfunction "1_P$1") (pintype "passive"))
    )
    (net (code "34") (name "/LSM1_SDO") (class "Default")
      (node (ref "LSM1") (pin "P$7") (pinfunction "P$7_SDO_P$7") (pintype "bidirectional"))
      (node (ref "U$10") (pin "2") (pinfunction "2_2") (pintype "passive"))
    )
    (net (code "35") (name "/LSM1_VDD") (class "Default")
      (node (ref "C12") (pin "1") (pinfunction "1_1") (pintype "passive"))
      (node (ref "C13") (pin "1") (pinfunction "1_1") (pintype "passive"))
      (node (ref "LSM1") (pin "P$1") (pinfunction "P$1_VDD_IO_P$1") (pintype "power_in"))
      (node (ref "LSM1") (pin "P$14") (pinfunction "P$14_VDD_P$14") (pintype "power_in"))
      (node (ref "LSM1") (pin "P$8") (pinfunction "P$8_CS_P$8") (pintype "bidirectional"))
      (node (ref "LSM1_HEADER") (pin "P$4") (pinfunction "4_P$4") (pintype "passive"))
      (node (ref "U$10") (pin "3") (pinfunction "3_3") (pintype "passive"))
    )
    (net (code "36") (name "/LSM2_GND") (class "Default")
      (node (ref "C16") (pin "2") (pinfunction "2_2") (pintype "passive"))
      (node (ref "C17") (pin "2") (pinfunction "2_2") (pintype "passive"))
      (node (ref "C18") (pin "2") (pinfunction "2_2") (pintype "passive"))
      (node (ref "LSM2") (pin "P$10") (pinfunction "P$10_GND_P$10") (pintype "bidirectional"))
      (node (ref "LSM2") (pin "P$12") (pinfunction "P$12_GND_P$12") (pintype "bidirectional"))
      (node (ref "LSM2") (pin "P$13") (pinfunction "P$13_GND_P$13") (pintype "bidirectional"))
      (node (ref "LSM2") (pin "P$16") (pinfunction "P$16_GND_P$16") (pintype "bidirectional"))
      (node (ref "LSM2") (pin "P$5") (pinfunction "P$5_GND_P$5") (pintype "power_in"))
      (node (ref "LSM2_HEADER") (pin "P$2") (pinfunction "2_P$2") (pintype "passive"))
      (node (ref "U$8") (pin "3") (pinfunction "3_3") (pintype "passive"))
    )
    (net (code "37") (name "/LSM2_SCL") (class "Default")
      (node (ref "LSM2") (pin "P$4") (pinfunction "P$4_SCL/SPC_P$4") (pintype "bidirectional"))
      (node (ref "LSM2_HEADER") (pin "P$3") (pinfunction "3_P$3") (pintype "passive"))
    )
    (net (code "38") (name "/LSM2_SDA") (class "Default")
      (node (ref "LSM2") (pin "P$6") (pinfunction "P$6_SDA/SDI_P$6") (pintype "bidirectional"))
      (node (ref "LSM2_HEADER") (pin "P$1") (pinfunction "1_P$1") (pintype "passive"))
    )
    (net (code "39") (name "/LSM2_SDO") (class "Default")
      (node (ref "LSM2") (pin "P$7") (pinfunction "P$7_SDO_P$7") (pintype "bidirectional"))
      (node (ref "U$8") (pin "2") (pinfunction "2_2") (pintype "passive"))
    )
    (net (code "40") (name "/LSM2_VDD") (class "Default")
      (node (ref "C17") (pin "1") (pinfunction "1_1") (pintype "passive"))
      (node (ref "C18") (pin "1") (pinfunction "1_1") (pintype "passive"))
      (node (ref "LSM2") (pin "P$1") (pinfunction "P$1_VDD_IO_P$1") (pintype "power_in"))
      (node (ref "LSM2") (pin "P$14") (pinfunction "P$14_VDD_P$14") (pintype "power_in"))
      (node (ref "LSM2") (pin "P$8") (pinfunction "P$8_CS_P$8") (pintype "bidirectional"))
      (node (ref "LSM2_HEADER") (pin "P$4") (pinfunction "4_P$4") (pintype "passive"))
      (node (ref "U$8") (pin "1") (pinfunction "1_1") (pintype "passive"))
    )
    (net (code "41") (name "/LSM3_GND") (class "Default")
      (node (ref "C25") (pin "2") (pinfunction "2_2") (pintype "passive"))
      (node (ref "C26") (pin "2") (pinfunction "2_2") (pintype "passive"))
      (node (ref "C27") (pin "2") (pinfunction "2_2") (pintype "passive"))
      (node (ref "LSM3") (pin "P$10") (pinfunction "P$10_GND_P$10") (pintype "bidirectional"))
      (node (ref "LSM3") (pin "P$12") (pinfunction "P$12_GND_P$12") (pintype "bidirectional"))
      (node (ref "LSM3") (pin "P$13") (pinfunction "P$13_GND_P$13") (pintype "bidirectional"))
      (node (ref "LSM3") (pin "P$16") (pinfunction "P$16_GND_P$16") (pintype "bidirectional"))
      (node (ref "LSM3") (pin "P$5") (pinfunction "P$5_GND_P$5") (pintype "power_in"))
      (node (ref "LSM3_HEADER") (pin "P$2") (pinfunction "2_P$2") (pintype "passive"))
      (node (ref "U$18") (pin "1") (pinfunction "1_1") (pintype "passive"))
    )
    (net (code "42") (name "/LSM3_SCL") (class "Default")
      (node (ref "LSM3") (pin "P$4") (pinfunction "P$4_SCL/SPC_P$4") (pintype "bidirectional"))
      (node (ref "LSM3_HEADER") (pin "P$3") (pinfunction "3_P$3") (pintype "passive"))
    )
    (net (code "43") (name "/LSM3_SDA") (class "Default")
      (node (ref "LSM3") (pin "P$6") (pinfunction "P$6_SDA/SDI_P$6") (pintype "bidirectional"))
      (node (ref "LSM3_HEADER") (pin "P$1") (pinfunction "1_P$1") (pintype "passive"))
    )
    (net (code "44") (name "/LSM3_SDO") (class "Default")
      (node (ref "LSM3") (pin "P$7") (pinfunction "P$7_SDO_P$7") (pintype "bidirectional"))
      (node (ref "U$18") (pin "2") (pinfunction "2_2") (pintype "passive"))
    )
    (net (code "45") (name "/LSM3_VDD") (class "Default")
      (node (ref "C26") (pin "1") (pinfunction "1_1") (pintype "passive"))
      (node (ref "C27") (pin "1") (pinfunction "1_1") (pintype "passive"))
      (node (ref "LSM3") (pin "P$1") (pinfunction "P$1_VDD_IO_P$1") (pintype "power_in"))
      (node (ref "LSM3") (pin "P$14") (pinfunction "P$14_VDD_P$14") (pintype "power_in"))
      (node (ref "LSM3") (pin "P$8") (pinfunction "P$8_CS_P$8") (pintype "bidirectional"))
      (node (ref "LSM3_HEADER") (pin "P$4") (pinfunction "4_P$4") (pintype "passive"))
      (node (ref "U$18") (pin "3") (pinfunction "3_3") (pintype "passive"))
    )
    (net (code "46") (name "/LSM4_GND") (class "Default")
      (node (ref "C29") (pin "2") (pinfunction "2_2") (pintype "passive"))
      (node (ref "C30") (pin "2") (pinfunction "2_2") (pintype "passive"))
      (node (ref "C31") (pin "2") (pinfunction "2_2") (pintype "passive"))
      (node (ref "LSM4") (pin "P$10") (pinfunction "P$10_GND_P$10") (pintype "bidirectional"))
      (node (ref "LSM4") (pin "P$12") (pinfunction "P$12_GND_P$12") (pintype "bidirectional"))
      (node (ref "LSM4") (pin "P$13") (pinfunction "P$13_GND_P$13") (pintype "bidirectional"))
      (node (ref "LSM4") (pin "P$16") (pinfunction "P$16_GND_P$16") (pintype "bidirectional"))
      (node (ref "LSM4") (pin "P$5") (pinfunction "P$5_GND_P$5") (pintype "power_in"))
      (node (ref "LSM4_HEADER") (pin "P$2") (pinfunction "2_P$2") (pintype "passive"))
      (node (ref "U$19") (pin "3") (pinfunction "3_3") (pintype "passive"))
    )
    (net (code "47") (name "/LSM4_SCL") (class "Default")
      (node (ref "LSM4") (pin "P$4") (pinfunction "P$4_SCL/SPC_P$4") (pintype "bidirectional"))
      (node (ref "LSM4_HEADER") (pin "P$3") (pinfunction "3_P$3") (pintype "passive"))
    )
    (net (code "48") (name "/LSM4_SDA") (class "Default")
      (node (ref "LSM4") (pin "P$6") (pinfunction "P$6_SDA/SDI_P$6") (pintype "bidirectional"))
      (node (ref "LSM4_HEADER") (pin "P$1") (pinfunction "1_P$1") (pintype "passive"))
    )
    (net (code "49") (name "/LSM4_SDO") (class "Default")
      (node (ref "LSM4") (pin "P$7") (pinfunction "P$7_SDO_P$7") (pintype "bidirectional"))
      (node (ref "U$19") (pin "2") (pinfunction "2_2") (pintype "passive"))
    )
    (net (code "50") (name "/LSM4_VDD") (class "Default")
      (node (ref "C30") (pin "1") (pinfunction "1_1") (pintype "passive"))
      (node (ref "C31") (pin "1") (pinfunction "1_1") (pintype "passive"))
      (node (ref "LSM4") (pin "P$1") (pinfunction "P$1_VDD_IO_P$1") (pintype "power_in"))
      (node (ref "LSM4") (pin "P$14") (pinfunction "P$14_VDD_P$14") (pintype "power_in"))
      (node (ref "LSM4") (pin "P$8") (pinfunction "P$8_CS_P$8") (pintype "bidirectional"))
      (node (ref "LSM4_HEADER") (pin "P$4") (pinfunction "4_P$4") (pintype "passive"))
      (node (ref "U$19") (pin "1") (pinfunction "1_1") (pintype "passive"))
    )
    (net (code "51") (name "/MISO") (class "Default")
      (node (ref "J1") (pin "1") (pinfunction "1_1") (pintype "passive"))
      (node (ref "MAX1") (pin "7") (pinfunction "SO_7") (pintype "bidirectional"))
      (node (ref "MAX2") (pin "7") (pinfunction "SO_7") (pintype "bidirectional"))
      (node (ref "U$1") (pin "MISO7") (pinfunction "DATA_OUT_MISO_MISO7") (pintype "output"))
      (node (ref "U$14") (pin "P$7_MISO") (pinfunction "DATA_OUT_MISO_P$7_MISO") (pintype "output"))
      (node (ref "U1") (pin "16") (pinfunction "PB4(MISO)_16") (pintype "bidirectional"))
    )
    (net (code "52") (name "/MOSI") (class "Default")
      (node (ref "J1") (pin "4") (pinfunction "4_4") (pintype "passive"))
      (node (ref "U$1") (pin "MOSI3") (pinfunction "DATA_IN_MOSI_MOSI3") (pintype "input"))
      (node (ref "U$14") (pin "P$3_MOSI") (pinfunction "DATA_IN_MOSI_P$3_MOSI") (pintype "input"))
      (node (ref "U1") (pin "15") (pinfunction "PB3(MOSI/OC2)_15") (pintype "bidirectional"))
    )
    (net (code "53") (name "/NC1") (class "Default")
      (node (ref "R5") (pin "1") (pinfunction "1_1") (pintype "passive"))
      (node (ref "U$1") (pin "NC1") (pinfunction "DAT1_NC_NC1") (pintype "bidirectional"))
      (node (ref "U$14") (pin "P$1_RSV") (pinfunction "DAT1_NC_P$1_RSV") (pintype "bidirectional"))
    )
    (net (code "54") (name "/PD3") (class "Default")
      (node (ref "U$7") (pin "1") (pinfunction "1_1") (pintype "passive"))
      (node (ref "U1") (pin "1") (pinfunction "PD3(INT1)_1") (pintype "bidirectional"))
    )
    (net (code "55") (name "/PD7") (class "Default")
      (node (ref "U$6") (pin "1") (pinfunction "P$1_1") (pintype "bidirectional"))
      (node (ref "U1") (pin "11") (pinfunction "PD7(AIN1)_11") (pintype "bidirectional"))
    )
    (net (code "56") (name "/RES") (class "Default")
      (node (ref "I2C_HEADER") (pin "1") (pinfunction "1_1") (pintype "passive"))
      (node (ref "U$7") (pin "2") (pinfunction "2_2") (pintype "passive"))
      (node (ref "U1") (pin "2") (pinfunction "PD4(XCK/T0)_2") (pintype "bidirectional"))
    )
    (net (code "57") (name "/RES8") (class "Default")
      (node (ref "R4") (pin "1") (pinfunction "1_1") (pintype "passive"))
      (node (ref "U$1") (pin "RES8") (pinfunction "DAT2_RES_RES8") (pintype "bidirectional"))
      (node (ref "U$14") (pin "P$8_RSV") (pinfunction "DAT2_RES_P$8_RSV") (pintype "bidirectional"))
    )
    (net (code "58") (name "/RESET") (class "Default")
      (node (ref "C5") (pin "2") (pinfunction "2_2") (pintype "passive"))
      (node (ref "J1") (pin "5") (pinfunction "5_5") (pintype "passive"))
      (node (ref "R6") (pin "1") (pinfunction "1_1") (pintype "passive"))
      (node (ref "RESET") (pin "S$1") (pinfunction "S1_S$1") (pintype "passive"))
      (node (ref "U1") (pin "29") (pinfunction "PC6(/RESET)_29") (pintype "bidirectional"))
    )
    (net (code "59") (name "/SCK") (class "Default")
      (node (ref "J1") (pin "3") (pinfunction "3_3") (pintype "passive"))
      (node (ref "MAX1") (pin "5") (pinfunction "SCK_5") (pintype "bidirectional"))
      (node (ref "MAX2") (pin "5") (pinfunction "SCK_5") (pintype "bidirectional"))
      (node (ref "U$1") (pin "SCK5") (pinfunction "SCLK_SCK5") (pintype "input"))
      (node (ref "U$14") (pin "P$5_SCK") (pinfunction "SCLK_P$5_SCK") (pintype "input"))
      (node (ref "U1") (pin "17") (pinfunction "PB5(SCK)_17") (pintype "bidirectional"))
    )
    (net (code "60") (name "/SCL") (class "Default")
      (node (ref "ACCEL1") (pin "3") (pinfunction "3_3") (pintype "passive"))
      (node (ref "ACCEL2") (pin "3") (pinfunction "3_3") (pintype "passive"))
      (node (ref "DS3231M") (pin "8") (pinfunction "P$8_SCL_8") (pintype "bidirectional"))
      (node (ref "I2C_HEADER") (pin "5") (pinfunction "5_5") (pintype "passive"))
      (node (ref "R7") (pin "1") (pinfunction "1_1") (pintype "passive"))
      (node (ref "U1") (pin "28") (pinfunction "PC5(ADC5/SCL)_28") (pintype "bidirectional"))
    )
    (net (code "61") (name "/SDA") (class "Default")
      (node (ref "ACCEL1") (pin "4") (pinfunction "4_4") (pintype "passive"))
      (node (ref "ACCEL2") (pin "4") (pinfunction "4_4") (pintype "passive"))
      (node (ref "DS3231M") (pin "7") (pinfunction "P$7_SDA_7") (pintype "bidirectional"))
      (node (ref "I2C_HEADER") (pin "4") (pinfunction "4_4") (pintype "passive"))
      (node (ref "R8") (pin "1") (pinfunction "1_1") (pintype "passive"))
      (node (ref "U1") (pin "27") (pinfunction "PC4(ADC4/SDA)_27") (pintype "bidirectional"))
    )
    (net (code "62") (name "/TO_FTDI_RX") (class "Default")
      (node (ref "JP1") (pin "5") (pinfunction "5_5") (pintype "passive"))
      (node (ref "U1") (pin "31") (pinfunction "PD1(TXD)_31") (pintype "bidirectional"))
    )
    (net (code "63") (name "/TO_FTDI_TX") (class "Default")
      (node (ref "JP1") (pin "4") (pinfunction "4_4") (pintype "passive"))
      (node (ref "U1") (pin "30") (pinfunction "PD0(RXD)_30") (pintype "bidirectional"))
    )
    (net (code "64") (name "/VBAT") (class "Default")
      (node (ref "CR1220_BATTERY") (pin "P$1") (pinfunction "VBAT_P$1") (pintype "power_in"))
      (node (ref "CR1220_BATTERY") (pin "P$2") (pinfunction "P$2_P$2") (pintype "power_in"))
      (node (ref "DS3231M") (pin "6") (pinfunction "P$6_VBAT_6") (pintype "bidirectional"))
    )
    (net (code "65") (name "/VRAW") (class "Default")
      (node (ref "C1") (pin "+") (pinfunction "+_+") (pintype "passive"))
      (node (ref "MCP1700T-3302") (pin "3") (pinfunction "VIN_3") (pintype "input"))
      (node (ref "X1") (pin "2") (pinfunction "S_2") (pintype "passive"))
    )
    (net (code "66") (name "/~{SLEEP2}") (class "Default")
      (node (ref "A139_HALL2") (pin "P$5") (pinfunction "P$5_P$5") (pintype "bidirectional"))
      (node (ref "R10") (pin "2") (pinfunction "2_2") (pintype "passive"))
    )
    (net (code "67") (name "/~{SLEEP3}") (class "Default")
      (node (ref "A139_HALL3") (pin "P$5") (pinfunction "P$5_P$5") (pintype "bidirectional"))
      (node (ref "R12") (pin "2") (pinfunction "2_2") (pintype "passive"))
    )
    (net (code "68") (name "/~{SLEEP4}") (class "Default")
      (node (ref "A139_HALL4") (pin "P$5") (pinfunction "P$5_P$5") (pintype "bidirectional"))
      (node (ref "R13") (pin "2") (pinfunction "2_2") (pintype "passive"))
    )
    (net (code "69") (name "/~{SLEEP}") (class "Default")
      (node (ref "A139_HALL1") (pin "P$5") (pinfunction "P$5_P$5") (pintype "bidirectional"))
      (node (ref "R11") (pin "2") (pinfunction "2_2") (pintype "passive"))
    )
    (net (code "70") (name "GND") (class "Default")
      (node (ref "ACCEL1") (pin "2") (pinfunction "2_2") (pintype "passive"))
      (node (ref "ACCEL2") (pin "2") (pinfunction "2_2") (pintype "passive"))
      (node (ref "BUTTON1") (pin "S$1") (pinfunction "S1_S$1") (pintype "passive"))
      (node (ref "C1") (pin "-") (pinfunction "-_-") (pintype "passive"))
      (node (ref "C2") (pin "-") (pinfunction "-_-") (pintype "passive"))
      (node (ref "C20") (pin "1") (pinfunction "1_1") (pintype "passive"))
      (node (ref "C3") (pin "2") (pinfunction "2_2") (pintype "passive"))
      (node (ref "C4") (pin "2") (pinfunction "2_2") (pintype "passive"))
      (node (ref "C7") (pin "2") (pinfunction "2_2") (pintype "passive"))
      (node (ref "C9") (pin "1") (pinfunction "1_1") (pintype "passive"))
      (node (ref "CR1220_BATTERY") (pin "GND") (pinfunction "GND_GND") (pintype "power_in"))
      (node (ref "DS3231M") (pin "5") (pinfunction "P$5_GND_5") (pintype "power_in"))
      (node (ref "GROUND_CON") (pin "1") (pinfunction "P$1_1") (pintype "bidirectional"))
      (node (ref "I2C_HEADER") (pin "3") (pinfunction "3_3") (pintype "passive"))
      (node (ref "J1") (pin "6") (pinfunction "6_6") (pintype "passive"))
      (node (ref "JP1") (pin "1") (pinfunction "1_1") (pintype "passive"))
      (node (ref "JP1") (pin "2") (pinfunction "2_2") (pintype "passive"))
      (node (ref "LED1") (pin "C") (pinfunction "C_C") (pintype "passive"))
      (node (ref "LED2") (pin "C") (pinfunction "C_C") (pintype "passive"))
      (node (ref "MCP1700T-3302") (pin "1") (pinfunction "GND_1") (pintype "passive"))
      (node (ref "RESET") (pin "P$1") (pinfunction "P1_P$1") (pintype "passive"))
      (node (ref "U$1") (pin "GND6") (pinfunction "VSS_GND_GND6") (pintype "power_in"))
      (node (ref "U$1") (pin "MNT1") (pinfunction "GND1_MNT1") (pintype "power_in"))
      (node (ref "U$1") (pin "MNT2") (pinfunction "GND2_MNT2") (pintype "power_in"))
      (node (ref "U$1") (pin "MNT3") (pinfunction "GND3_MNT3") (pintype "power_in"))
      (node (ref "U$1") (pin "MNT4") (pinfunction "GND4_MNT4") (pintype "power_in"))
      (node (ref "U$14") (pin "P$10") (pinfunction "GND2_P$10") (pintype "power_in"))
      (node (ref "U$14") (pin "P$13") (pinfunction "GND3_P$13") (pintype "power_in"))
      (node (ref "U$14") (pin "P$14") (pinfunction "GND4_P$14") (pintype "power_in"))
      (node (ref "U$14") (pin "P$6_GND") (pinfunction "VSS_GND_P$6_GND") (pintype "power_in"))
      (node (ref "U$14") (pin "P$9") (pinfunction "GND1_P$9") (pintype "power_in"))
      (node (ref "U1") (pin "3") (pinfunction "GND_3") (pintype "bidirectional"))
      (node (ref "U1") (pin "5") (pinfunction "GND_5") (pintype "bidirectional"))
      (node (ref "X1") (pin "1") (pinfunction "S_1") (pintype "passive"))
    )
    (net (code "71") (name "Net-(LED1-PadA)") (class "Default")
      (node (ref "LED1") (pin "A") (pinfunction "A_A") (pintype "passive"))
      (node (ref "R1") (pin "1") (pinfunction "1_1") (pintype "passive"))
    )
    (net (code "72") (name "Net-(LED2-PadA)") (class "Default")
      (node (ref "LED2") (pin "A") (pinfunction "A_A") (pintype "passive"))
      (node (ref "R2") (pin "1") (pinfunction "1_1") (pintype "passive"))
    )
    (net (code "73") (name "Net-(LSM1-P$2_SETC)") (class "Default")
      (node (ref "C10") (pin "2") (pinfunction "2_2") (pintype "passive"))
      (node (ref "LSM1") (pin "P$2") (pinfunction "P$2_SETC_P$2") (pintype "bidirectional"))
    )
    (net (code "74") (name "Net-(LSM1-P$3_SETP)") (class "Default")
      (node (ref "C10") (pin "1") (pinfunction "1_1") (pintype "passive"))
      (node (ref "LSM1") (pin "P$3") (pinfunction "P$3_SETP_P$3") (pintype "bidirectional"))
    )
    (net (code "75") (name "Net-(LSM1-P$15_C1)") (class "Default")
      (node (ref "C11") (pin "1") (pinfunction "1_1") (pintype "passive"))
      (node (ref "LSM1") (pin "P$15") (pinfunction "P$15_C1_P$15") (pintype "bidirectional"))
    )
    (net (code "76") (name "Net-(LSM2-P$2_SETC)") (class "Default")
      (node (ref "C15") (pin "2") (pinfunction "2_2") (pintype "passive"))
      (node (ref "LSM2") (pin "P$2") (pinfunction "P$2_SETC_P$2") (pintype "bidirectional"))
    )
    (net (code "77") (name "Net-(LSM2-P$3_SETP)") (class "Default")
      (node (ref "C15") (pin "1") (pinfunction "1_1") (pintype "passive"))
      (node (ref "LSM2") (pin "P$3") (pinfunction "P$3_SETP_P$3") (pintype "bidirectional"))
    )
    (net (code "78") (name "Net-(LSM2-P$15_C1)") (class "Default")
      (node (ref "C16") (pin "1") (pinfunction "1_1") (pintype "passive"))
      (node (ref "LSM2") (pin "P$15") (pinfunction "P$15_C1_P$15") (pintype "bidirectional"))
    )
    (net (code "79") (name "Net-(LSM3-P$2_SETC)") (class "Default")
      (node (ref "C24") (pin "2") (pinfunction "2_2") (pintype "passive"))
      (node (ref "LSM3") (pin "P$2") (pinfunction "P$2_SETC_P$2") (pintype "bidirectional"))
    )
    (net (code "80") (name "Net-(LSM3-P$3_SETP)") (class "Default")
      (node (ref "C24") (pin "1") (pinfunction "1_1") (pintype "passive"))
      (node (ref "LSM3") (pin "P$3") (pinfunction "P$3_SETP_P$3") (pintype "bidirectional"))
    )
    (net (code "81") (name "Net-(LSM3-P$15_C1)") (class "Default")
      (node (ref "C25") (pin "1") (pinfunction "1_1") (pintype "passive"))
      (node (ref "LSM3") (pin "P$15") (pinfunction "P$15_C1_P$15") (pintype "bidirectional"))
    )
    (net (code "82") (name "Net-(LSM4-P$2_SETC)") (class "Default")
      (node (ref "C28") (pin "2") (pinfunction "2_2") (pintype "passive"))
      (node (ref "LSM4") (pin "P$2") (pinfunction "P$2_SETC_P$2") (pintype "bidirectional"))
    )
    (net (code "83") (name "Net-(LSM4-P$3_SETP)") (class "Default")
      (node (ref "C28") (pin "1") (pinfunction "1_1") (pintype "passive"))
      (node (ref "LSM4") (pin "P$3") (pinfunction "P$3_SETP_P$3") (pintype "bidirectional"))
    )
    (net (code "84") (name "Net-(LSM4-P$15_C1)") (class "Default")
      (node (ref "C29") (pin "1") (pinfunction "1_1") (pintype "passive"))
      (node (ref "LSM4") (pin "P$15") (pinfunction "P$15_C1_P$15") (pintype "bidirectional"))
    )
    (net (code "85") (name "Net-(MAX1-T+)") (class "Default")
      (node (ref "C8") (pin "2") (pinfunction "2_2") (pintype "passive"))
      (node (ref "MAX1") (pin "3") (pinfunction "T+_3") (pintype "input"))
      (node (ref "U$3") (pin "2") (pinfunction "P$2_2") (pintype "bidirectional"))
    )
    (net (code "86") (name "Net-(MAX1-T-)") (class "Default")
      (node (ref "C8") (pin "1") (pinfunction "1_1") (pintype "passive"))
      (node (ref "MAX1") (pin "2") (pinfunction "T-_2") (pintype "input"))
      (node (ref "U$4") (pin "2") (pinfunction "P$2_2") (pintype "bidirectional"))
    )
    (net (code "87") (name "Net-(MAX2-T+)") (class "Default")
      (node (ref "C22") (pin "2") (pinfunction "2_2") (pintype "passive"))
      (node (ref "MAX2") (pin "3") (pinfunction "T+_3") (pintype "input"))
      (node (ref "U$13") (pin "2") (pinfunction "P$2_2") (pintype "bidirectional"))
    )
    (net (code "88") (name "Net-(MAX2-T-)") (class "Default")
      (node (ref "C22") (pin "1") (pinfunction "1_1") (pintype "passive"))
      (node (ref "MAX2") (pin "2") (pinfunction "T-_2") (pintype "input"))
      (node (ref "U$12") (pin "2") (pinfunction "P$2_2") (pintype "bidirectional"))
    )
    (net (code "89") (name "Net-(U$3-P$1)") (class "Default")
      (node (ref "U$2") (pin "P$1") (pinfunction "P$1_P$1") (pintype "bidirectional"))
      (node (ref "U$3") (pin "1") (pinfunction "P$1_1") (pintype "bidirectional"))
    )
    (net (code "90") (name "Net-(U$4-P$1)") (class "Default")
      (node (ref "U$2") (pin "P$2") (pinfunction "P$2_P$2") (pintype "bidirectional"))
      (node (ref "U$4") (pin "1") (pinfunction "P$1_1") (pintype "bidirectional"))
    )
    (net (code "91") (name "Net-(U$12-P$1)") (class "Default")
      (node (ref "U$12") (pin "1") (pinfunction "P$1_1") (pintype "bidirectional"))
      (node (ref "U$16") (pin "P$2") (pinfunction "P$2_P$2") (pintype "bidirectional"))
    )
    (net (code "92") (name "Net-(U$13-P$1)") (class "Default")
      (node (ref "U$13") (pin "1") (pinfunction "P$1_1") (pintype "bidirectional"))
      (node (ref "U$16") (pin "P$1") (pinfunction "P$1_P$1") (pintype "bidirectional"))
    )
    (net (code "93") (name "Net-(U$17-P$1)") (class "Default")
      (node (ref "U$17") (pin "1") (pinfunction "P$1_1") (pintype "bidirectional"))
      (node (ref "U1") (pin "20") (pinfunction "AREF_20") (pintype "bidirectional"))
    )
    (net (code "94") (name "Net-(U1-PC0(ADC0))") (class "Default")
      (node (ref "R16") (pin "1") (pinfunction "1_1") (pintype "passive"))
      (node (ref "U$15") (pin "1") (pinfunction "1_1") (pintype "passive"))
      (node (ref "U1") (pin "23") (pinfunction "PC0(ADC0)_23") (pintype "bidirectional"))
    )
    (net (code "95") (name "Net-(U1-PC1(ADC1))") (class "Default")
      (node (ref "R15") (pin "1") (pinfunction "1_1") (pintype "passive"))
      (node (ref "U$15") (pin "2") (pinfunction "2_2") (pintype "passive"))
      (node (ref "U1") (pin "24") (pinfunction "PC1(ADC1)_24") (pintype "bidirectional"))
    )
    (net (code "96") (name "VCC") (class "Default")
      (node (ref "ACCEL1") (pin "1") (pinfunction "1_1") (pintype "passive"))
      (node (ref "ACCEL2") (pin "1") (pinfunction "1_1") (pintype "passive"))
      (node (ref "C2") (pin "+") (pinfunction "+_+") (pintype "passive"))
      (node (ref "C20") (pin "2") (pinfunction "2_2") (pintype "passive"))
      (node (ref "C21") (pin "2") (pinfunction "2_2") (pintype "passive"))
      (node (ref "C3") (pin "1") (pinfunction "1_1") (pintype "passive"))
      (node (ref "C4") (pin "1") (pinfunction "1_1") (pintype "passive"))
      (node (ref "C6") (pin "2") (pinfunction "2_2") (pintype "passive"))
      (node (ref "C7") (pin "1") (pinfunction "1_1") (pintype "passive"))
      (node (ref "C9") (pin "2") (pinfunction "2_2") (pintype "passive"))
      (node (ref "DS3231M") (pin "2") (pinfunction "P$2_VCC_2") (pintype "power_in"))
      (node (ref "HALL1") (pin "1") (pinfunction "1_1") (pintype "passive"))
      (node (ref "HALL2") (pin "1") (pinfunction "1_1") (pintype "passive"))
      (node (ref "I2C_HEADER") (pin "2") (pinfunction "2_2") (pintype "passive"))
      (node (ref "INDUCTOR") (pin "P$2") (pinfunction "2_P$2") (pintype "passive"))
      (node (ref "J1") (pin "2") (pinfunction "2_2") (pintype "passive"))
      (node (ref "JP1") (pin "3") (pinfunction "3_3") (pintype "passive"))
      (node (ref "MAX1") (pin "4") (pinfunction "VCC_4") (pintype "power_in"))
      (node (ref "MAX2") (pin "4") (pinfunction "VCC_4") (pintype "power_in"))
      (node (ref "MCP1700T-3302") (pin "2") (pinfunction "VOUT_2") (pintype "output"))
      (node (ref "R15") (pin "2") (pinfunction "2_2") (pintype "passive"))
      (node (ref "R16") (pin "2") (pinfunction "2_2") (pintype "passive"))
      (node (ref "R4") (pin "2") (pinfunction "2_2") (pintype "passive"))
      (node (ref "R5") (pin "2") (pinfunction "2_2") (pintype "passive"))
      (node (ref "R6") (pin "2") (pinfunction "2_2") (pintype "passive"))
      (node (ref "R7") (pin "2") (pinfunction "2_2") (pintype "passive"))
      (node (ref "R8") (pin "2") (pinfunction "2_2") (pintype "passive"))
      (node (ref "R9") (pin "2") (pinfunction "2_2") (pintype "passive"))
      (node (ref "U$1") (pin "VDD4") (pinfunction "VDD_VDD4") (pintype "power_in"))
      (node (ref "U$14") (pin "P$4_VDD") (pinfunction "VDD_P$4_VDD") (pintype "power_in"))
      (node (ref "U1") (pin "4") (pinfunction "VCC_4") (pintype "bidirectional"))
      (node (ref "U1") (pin "6") (pinfunction "VCC_6") (pintype "bidirectional"))
    )
    (net (code "97") (name "unconnected-(BUTTON1-PadP)") (class "Default")
      (node (ref "BUTTON1") (pin "P") (pinfunction "P_P") (pintype "passive"))
    )
    (net (code "98") (name "unconnected-(BUTTON1-PadS)") (class "Default")
      (node (ref "BUTTON1") (pin "S") (pinfunction "S_S") (pintype "passive"))
    )
    (net (code "99") (name "unconnected-(DS3231M-P$3_INT-Pad3)") (class "Default")
      (node (ref "DS3231M") (pin "3") (pinfunction "P$3_INT_3") (pintype "bidirectional"))
    )
    (net (code "100") (name "unconnected-(DS3231M-P$4_RST-Pad4)") (class "Default")
      (node (ref "DS3231M") (pin "4") (pinfunction "P$4_RST_4") (pintype "bidirectional"))
    )
    (net (code "101") (name "unconnected-(LSM1-P$9_INT2-PadP$9)") (class "Default")
      (node (ref "LSM1") (pin "P$9") (pinfunction "P$9_INT2_P$9") (pintype "bidirectional"))
    )
    (net (code "102") (name "unconnected-(LSM1-P$11_INT1-PadP$11)") (class "Default")
      (node (ref "LSM1") (pin "P$11") (pinfunction "P$11_INT1_P$11") (pintype "bidirectional"))
    )
    (net (code "103") (name "unconnected-(LSM2-P$9_INT2-PadP$9)") (class "Default")
      (node (ref "LSM2") (pin "P$9") (pinfunction "P$9_INT2_P$9") (pintype "bidirectional"))
    )
    (net (code "104") (name "unconnected-(LSM2-P$11_INT1-PadP$11)") (class "Default")
      (node (ref "LSM2") (pin "P$11") (pinfunction "P$11_INT1_P$11") (pintype "bidirectional"))
    )
    (net (code "105") (name "unconnected-(LSM3-P$9_INT2-PadP$9)") (class "Default")
      (node (ref "LSM3") (pin "P$9") (pinfunction "P$9_INT2_P$9") (pintype "bidirectional"))
    )
    (net (code "106") (name "unconnected-(LSM3-P$11_INT1-PadP$11)") (class "Default")
      (node (ref "LSM3") (pin "P$11") (pinfunction "P$11_INT1_P$11") (pintype "bidirectional"))
    )
    (net (code "107") (name "unconnected-(LSM4-P$9_INT2-PadP$9)") (class "Default")
      (node (ref "LSM4") (pin "P$9") (pinfunction "P$9_INT2_P$9") (pintype "bidirectional"))
    )
    (net (code "108") (name "unconnected-(LSM4-P$11_INT1-PadP$11)") (class "Default")
      (node (ref "LSM4") (pin "P$11") (pinfunction "P$11_INT1_P$11") (pintype "bidirectional"))
    )
    (net (code "109") (name "unconnected-(MAX1-DNC-Pad8)") (class "Default")
      (node (ref "MAX1") (pin "8") (pinfunction "DNC_8") (pintype "no_connect"))
    )
    (net (code "110") (name "unconnected-(MAX2-DNC-Pad8)") (class "Default")
      (node (ref "MAX2") (pin "8") (pinfunction "DNC_8") (pintype "no_connect"))
    )
    (net (code "111") (name "unconnected-(RESET-PadP)") (class "Default")
      (node (ref "RESET") (pin "P") (pinfunction "P_P") (pintype "passive"))
    )
    (net (code "112") (name "unconnected-(RESET-PadS)") (class "Default")
      (node (ref "RESET") (pin "S") (pinfunction "S_S") (pintype "passive"))
    )
    (net (code "113") (name "unconnected-(U$1-CARD_DETECT-PadCARD_DETECT1)") (class "Default")
      (node (ref "U$1") (pin "CARD_DETECT1") (pinfunction "CARD_DETECT_CARD_DETECT1") (pintype "passive"))
    )
    (net (code "114") (name "unconnected-(U$1-CARD_DETECT1-PadCARD_DETECT2)") (class "Default")
      (node (ref "U$1") (pin "CARD_DETECT2") (pinfunction "CARD_DETECT1_CARD_DETECT2") (pintype "passive"))
    )
    (net (code "115") (name "unconnected-(U$14-CARD_DETECT-PadP$11_CARD_DETECT1)") (class "Default")
      (node (ref "U$14") (pin "P$11_CARD_DETECT1") (pinfunction "CARD_DETECT_P$11_CARD_DETECT1") (pintype "passive"))
    )
    (net (code "116") (name "unconnected-(U$14-CARD_DETECT1-PadP$12_CARD_DETECT2)") (class "Default")
      (node (ref "U$14") (pin "P$12_CARD_DETECT2") (pinfunction "CARD_DETECT1_P$12_CARD_DETECT2") (pintype "passive"))
    )
    (net (code "117") (name "unconnected-(U1-PB7(XTAL2{slash}TOSC2)-Pad8)") (class "Default")
      (node (ref "U1") (pin "8") (pinfunction "PB7(XTAL2/TOSC2)_8") (pintype "bidirectional"))
    )
  )
)
